# Power_Input.net
KiCad netlist of a schematic drawn in Altium Designer
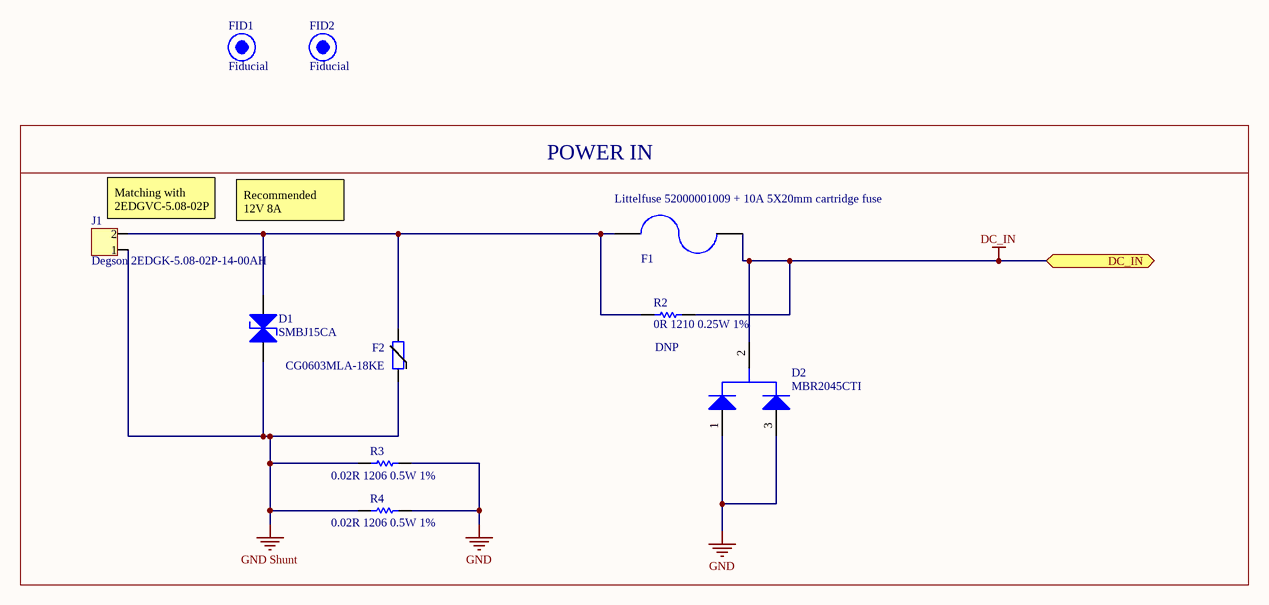
[diagram p0: Power_Input.SchDoc]

(export (version "E")
  (design (tool "Eeschema 10.0.6"))
  (components
    (comp (ref "D1")
      (value "SMBJ15CA")
      (footprint "PCB-acsqsz06h0bi34fqghyj-1")
      (description "SMBJ15 Series 24.4 V 600 W Bi-Directional Transient Voltage Suppressor-DO-214AA")
      (libsource (lib "CommunityVault") (part "SYM-f09b39914f642f5c-1"))
    )
    (comp (ref "D2")
      (value "MBR2045CTI")
      (footprint "INF-PG-TO251-3-11")
      (description "Schottky Rectifier TO251 Tube 75PCS")
      (fields (field (name "MANUFACTURER PART NUMBER") "MBR2045CTI"))
      (libsource (lib "CommunityVault") (part "CMP-d2061815e9930dc1-1"))
    )
    (comp (ref "F1")
      (value "Littelfuse 52000001009 + 10A 5X20mm cartridge fuse")
      (footprint "PCB-ute3syh1w8vttzwbvd5x-1")
      (description "Fuse Clip with Ear Through Hole Bulk + 10A 5X20mm cartridge fuse")
      (fields (field (name "MANUFACTURER PART NUMBER") "FC-201BRIGHTTIN"))
      (libsource (lib "CommunityVault") (part "CMP-e4812c024ed53b46-3"))
    )
    (comp (ref "F2")
      (value "CG0603MLA-18KE")
      (footprint "CAPC1608X60X35NL10T15")
      (description "Var MOV 14VAC 18VDC 30A 24.2V 0603 SMD Paper T/R Var MOV 14VAC 18VDC 30A 24.2V 0603 SMD Paper T/R")
      (libsource (lib "FavoritesLibrary") (part "SYM-234feae503b6fc88-1"))
    )
    (comp (ref "FID1")
      (value "Fiducial")
      (footprint "PCB-4cof372i0ax01akz57r7-1")
      (libsource (lib "FavoritesLibrary") (part "SYM-4cof372i0ax01akz57r7-1"))
    )
    (comp (ref "FID2")
      (value "Fiducial")
      (footprint "PCB-4cof372i0ax01akz57r7-1")
      (libsource (lib "FavoritesLibrary") (part "SYM-4cof372i0ax01akz57r7-1"))
    )
    (comp (ref "J1")
      (value "Degson 2EDGK-5.08-02P-14-00AH")
      (footprint "PCB-h4cyb3wxd4gf7j132tzl-1")
      (description "Terminal block, 5mm 2 Pos, through hole male.")
      (fields (field (name "MANUFACTURER PART NUMBER") "2EDGK-5.08-02P-14-00AH"))
      (libsource (lib "CommunityVault") (part "CMP-7a42b7ee166ba585-1"))
    )
    (comp (ref "R2")
      (value "0R 1210 0.25W 1%")
      (footprint "RESC3225X70X50NL20T20")
      (fields (field (name "DNP") "DNP"))
      (libsource (lib "CommunityVault") (part "CMP-2532823-2"))
    )
    (comp (ref "R3")
      (value "0.02R 1206 0.5W 1%")
      (footprint "CAPC3216X180X55ML20T25")
      (fields (field (name "MANUFACTURER PART NUMBER") "1-2176055-0") (field (name "POWER") "1/2W"))
      (libsource (lib "CommunityVault") (part "CMP-0abdc173b10ad57a-1"))
    )
    (comp (ref "R4")
      (value "0.02R 1206 0.5W 1%")
      (footprint "CAPC3216X180X55ML20T25")
      (fields (field (name "MANUFACTURER PART NUMBER") "1-2176055-0") (field (name "POWER") "1/2W"))
      (libsource (lib "CommunityVault") (part "CMP-0abdc173b10ad57a-1"))
    )
  )
  (nets
    (net (code "1") (name "DC_IN") (class "Default")
      (node (ref "D2") (pin "2") (pinfunction "K_2") (pintype "passive"))
      (node (ref "F1") (pin "2") (pinfunction "2_2") (pintype "passive"))
      (node (ref "R2") (pin "2") (pinfunction "2_2") (pintype "passive"))
    )
    (net (code "2") (name "GND") (class "Default")
      (node (ref "D2") (pin "1") (pinfunction "A1_1") (pintype "passive"))
      (node (ref "D2") (pin "3") (pinfunction "A2_3") (pintype "passive"))
      (node (ref "R3") (pin "1") (pinfunction "1_1") (pintype "passive"))
      (node (ref "R4") (pin "1") (pinfunction "1_1") (pintype "passive"))
    )
    (net (code "3") (name "GND Shunt") (class "Default")
      (node (ref "D1") (pin "1") (pinfunction "A_1") (pintype "passive"))
      (node (ref "F2") (pin "1") (pinfunction "1_1") (pintype "passive"))
      (node (ref "J1") (pin "1") (pinfunction "1_1") (pintype "passive"))
      (node (ref "R3") (pin "2") (pinfunction "2_2") (pintype "passive"))
      (node (ref "R4") (pin "2") (pinfunction "2_2") (pintype "passive"))
    )
    (net (code "4") (name "Net-(D1-K)") (class "Default")
      (node (ref "D1") (pin "2") (pinfunction "K_2") (pintype "passive"))
      (node (ref "F1") (pin "1") (pinfunction "1_1") (pintype "passive"))
      (node (ref "F2") (pin "2") (pinfunction "2_2") (pintype "passive"))
      (node (ref "J1") (pin "2") (pinfunction "2_2") (pintype "passive"))
      (node (ref "R2") (pin "1") (pinfunction "1_1") (pintype "passive"))
    )
  )
)
